# Motor4_PCIe.net
KiCad netlist of a schematic drawn in Altium Designer
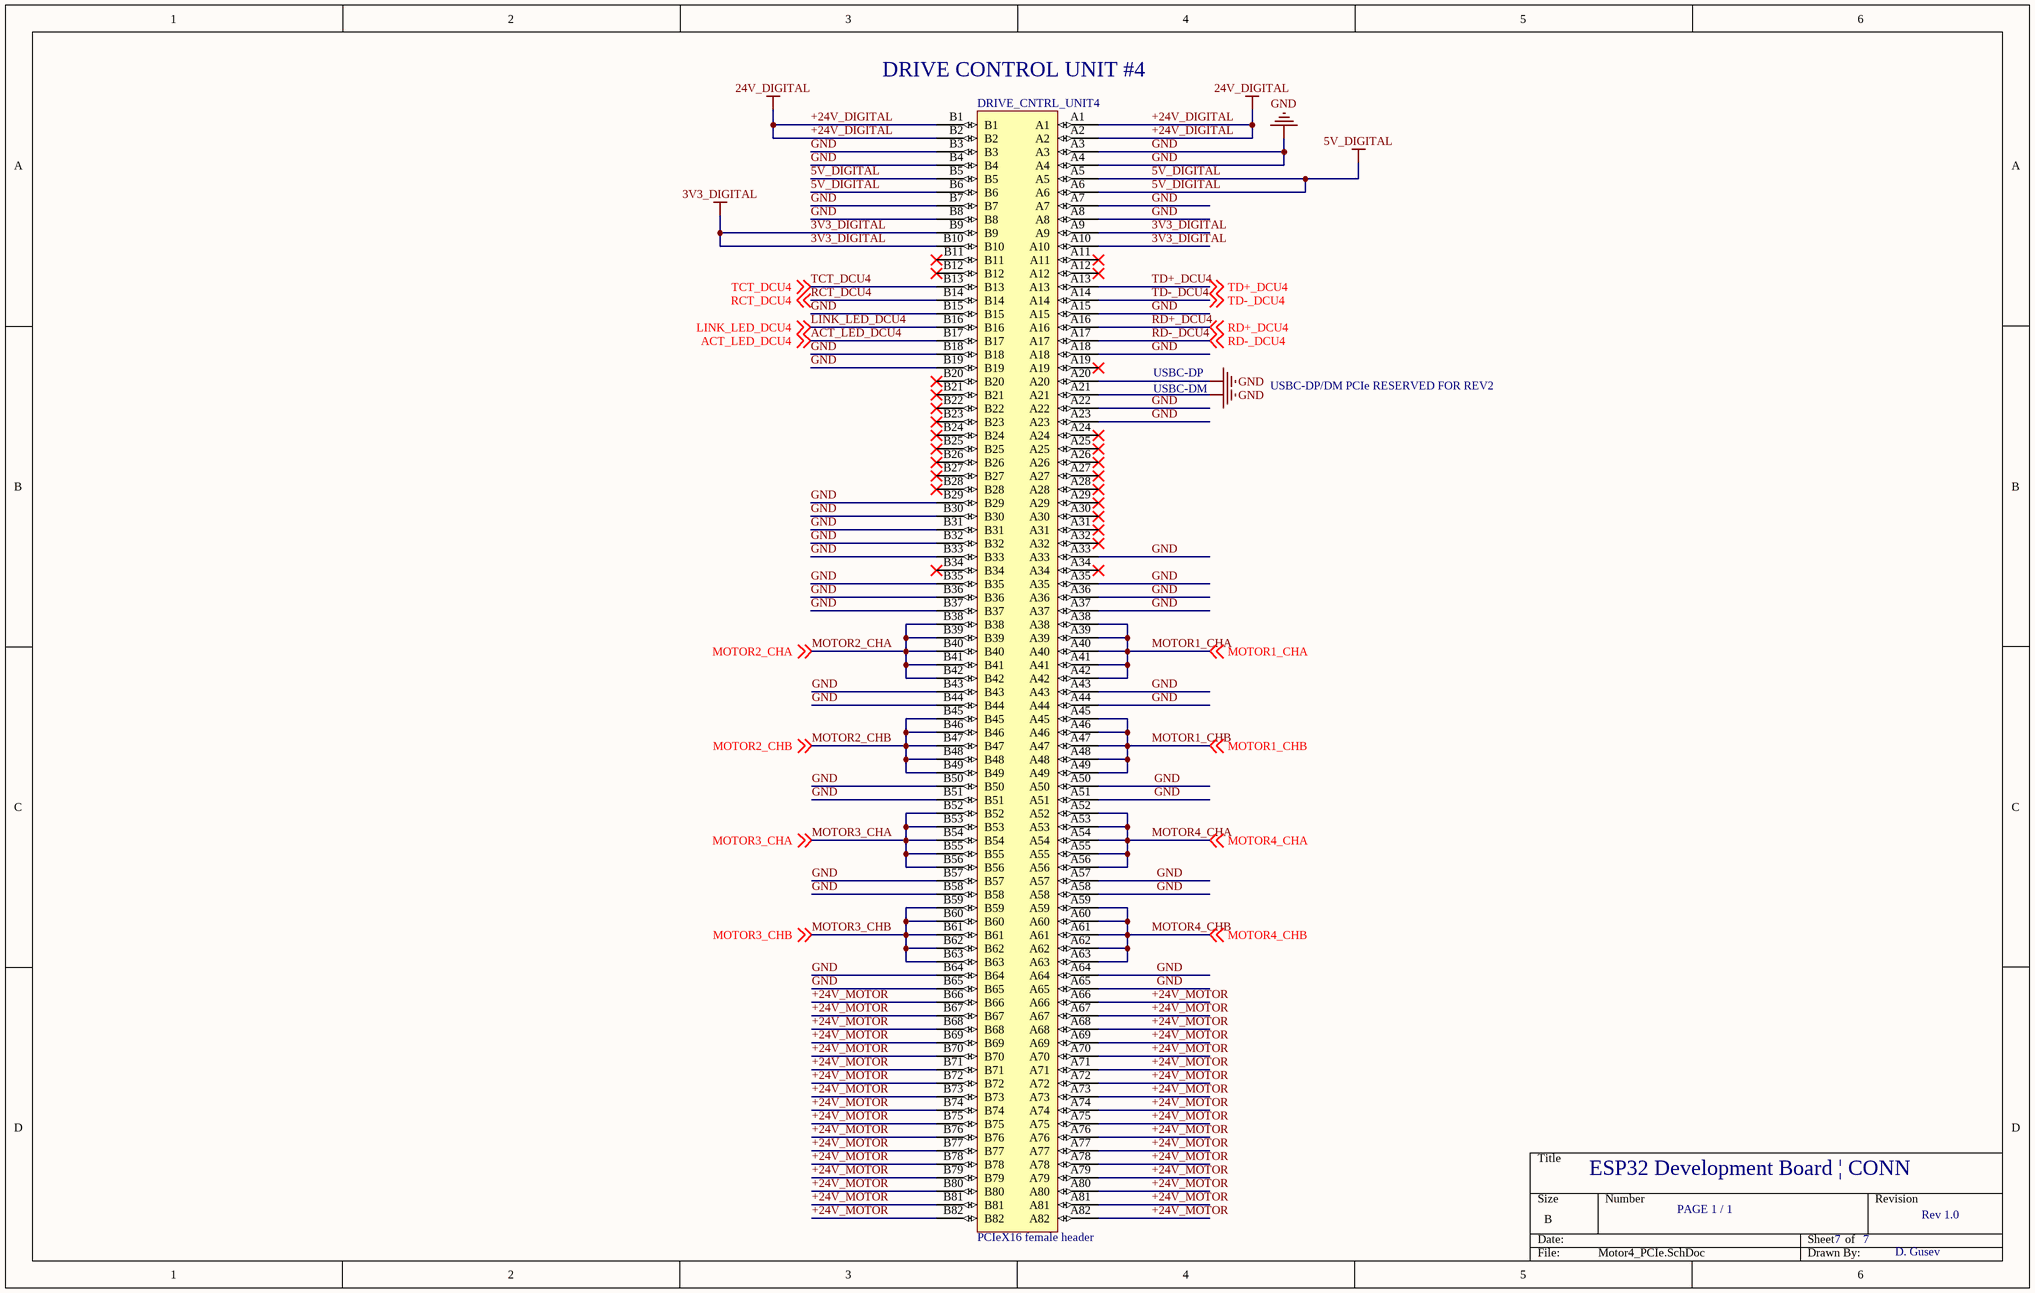
[diagram p0: Motor4_PCIe.SchDoc]

(export (version "E")
  (design (tool "Eeschema 10.0.6"))
  (components
    (comp (ref "DRIVE_CNTRL_UNIT4")
      (value "PCIeX16 female header")
      (footprint "SAMTEC_PCIE-164-02-X-D-TH")
      (description "164-position SAMTEC female header")
      (libsource (lib "ANTS-MotherBoard-B1") (part "PCIeX16 female header"))
    )
  )
  (nets
    (net (code "1") (name "/+24V_MOTOR") (class "Default")
      (node (ref "DRIVE_CNTRL_UNIT4") (pin "A66") (pinfunction "A66_A66") (pintype "bidirectional"))
      (node (ref "DRIVE_CNTRL_UNIT4") (pin "A67") (pinfunction "A67_A67") (pintype "bidirectional"))
      (node (ref "DRIVE_CNTRL_UNIT4") (pin "A68") (pinfunction "A68_A68") (pintype "bidirectional"))
      (node (ref "DRIVE_CNTRL_UNIT4") (pin "A69") (pinfunction "A69_A69") (pintype "bidirectional"))
      (node (ref "DRIVE_CNTRL_UNIT4") (pin "A70") (pinfunction "A70_A70") (pintype "bidirectional"))
      (node (ref "DRIVE_CNTRL_UNIT4") (pin "A71") (pinfunction "A71_A71") (pintype "bidirectional"))
      (node (ref "DRIVE_CNTRL_UNIT4") (pin "A72") (pinfunction "A72_A72") (pintype "bidirectional"))
      (node (ref "DRIVE_CNTRL_UNIT4") (pin "A73") (pinfunction "A73_A73") (pintype "bidirectional"))
      (node (ref "DRIVE_CNTRL_UNIT4") (pin "A74") (pinfunction "A74_A74") (pintype "bidirectional"))
      (node (ref "DRIVE_CNTRL_UNIT4") (pin "A75") (pinfunction "A75_A75") (pintype "bidirectional"))
      (node (ref "DRIVE_CNTRL_UNIT4") (pin "A76") (pinfunction "A76_A76") (pintype "bidirectional"))
      (node (ref "DRIVE_CNTRL_UNIT4") (pin "A77") (pinfunction "A77_A77") (pintype "bidirectional"))
      (node (ref "DRIVE_CNTRL_UNIT4") (pin "A78") (pinfunction "A78_A78") (pintype "bidirectional"))
      (node (ref "DRIVE_CNTRL_UNIT4") (pin "A79") (pinfunction "A79_A79") (pintype "bidirectional"))
      (node (ref "DRIVE_CNTRL_UNIT4") (pin "A80") (pinfunction "A80_A80") (pintype "bidirectional"))
      (node (ref "DRIVE_CNTRL_UNIT4") (pin "A81") (pinfunction "A81_A81") (pintype "bidirectional"))
      (node (ref "DRIVE_CNTRL_UNIT4") (pin "A82") (pinfunction "A82_A82") (pintype "bidirectional"))
      (node (ref "DRIVE_CNTRL_UNIT4") (pin "B66") (pinfunction "B66_B66") (pintype "bidirectional"))
      (node (ref "DRIVE_CNTRL_UNIT4") (pin "B67") (pinfunction "B67_B67") (pintype "bidirectional"))
      (node (ref "DRIVE_CNTRL_UNIT4") (pin "B68") (pinfunction "B68_B68") (pintype "bidirectional"))
      (node (ref "DRIVE_CNTRL_UNIT4") (pin "B69") (pinfunction "B69_B69") (pintype "bidirectional"))
      (node (ref "DRIVE_CNTRL_UNIT4") (pin "B70") (pinfunction "B70_B70") (pintype "bidirectional"))
      (node (ref "DRIVE_CNTRL_UNIT4") (pin "B71") (pinfunction "B71_B71") (pintype "bidirectional"))
      (node (ref "DRIVE_CNTRL_UNIT4") (pin "B72") (pinfunction "B72_B72") (pintype "bidirectional"))
      (node (ref "DRIVE_CNTRL_UNIT4") (pin "B73") (pinfunction "B73_B73") (pintype "bidirectional"))
      (node (ref "DRIVE_CNTRL_UNIT4") (pin "B74") (pinfunction "B74_B74") (pintype "bidirectional"))
      (node (ref "DRIVE_CNTRL_UNIT4") (pin "B75") (pinfunction "B75_B75") (pintype "bidirectional"))
      (node (ref "DRIVE_CNTRL_UNIT4") (pin "B76") (pinfunction "B76_B76") (pintype "bidirectional"))
      (node (ref "DRIVE_CNTRL_UNIT4") (pin "B77") (pinfunction "B77_B77") (pintype "bidirectional"))
      (node (ref "DRIVE_CNTRL_UNIT4") (pin "B78") (pinfunction "B78_B78") (pintype "bidirectional"))
      (node (ref "DRIVE_CNTRL_UNIT4") (pin "B79") (pinfunction "B79_B79") (pintype "bidirectional"))
      (node (ref "DRIVE_CNTRL_UNIT4") (pin "B80") (pinfunction "B80_B80") (pintype "bidirectional"))
      (node (ref "DRIVE_CNTRL_UNIT4") (pin "B81") (pinfunction "B81_B81") (pintype "bidirectional"))
      (node (ref "DRIVE_CNTRL_UNIT4") (pin "B82") (pinfunction "B82_B82") (pintype "bidirectional"))
    )
    (net (code "2") (name "3V3_DIGITAL") (class "Default")
      (node (ref "DRIVE_CNTRL_UNIT4") (pin "A10") (pinfunction "A10_A10") (pintype "bidirectional"))
      (node (ref "DRIVE_CNTRL_UNIT4") (pin "A9") (pinfunction "A9_A9") (pintype "bidirectional"))
      (node (ref "DRIVE_CNTRL_UNIT4") (pin "B10") (pinfunction "B10_B10") (pintype "bidirectional"))
      (node (ref "DRIVE_CNTRL_UNIT4") (pin "B9") (pinfunction "B9_B9") (pintype "bidirectional"))
    )
    (net (code "3") (name "5V_DIGITAL") (class "Default")
      (node (ref "DRIVE_CNTRL_UNIT4") (pin "A5") (pinfunction "A5_A5") (pintype "bidirectional"))
      (node (ref "DRIVE_CNTRL_UNIT4") (pin "A6") (pinfunction "A6_A6") (pintype "bidirectional"))
      (node (ref "DRIVE_CNTRL_UNIT4") (pin "B5") (pinfunction "B5_B5") (pintype "bidirectional"))
      (node (ref "DRIVE_CNTRL_UNIT4") (pin "B6") (pinfunction "B6_B6") (pintype "bidirectional"))
    )
    (net (code "4") (name "24V_DIGITAL") (class "Default")
      (node (ref "DRIVE_CNTRL_UNIT4") (pin "A1") (pinfunction "A1_A1") (pintype "bidirectional"))
      (node (ref "DRIVE_CNTRL_UNIT4") (pin "A2") (pinfunction "A2_A2") (pintype "bidirectional"))
      (node (ref "DRIVE_CNTRL_UNIT4") (pin "B1") (pinfunction "B1_B1") (pintype "bidirectional"))
      (node (ref "DRIVE_CNTRL_UNIT4") (pin "B2") (pinfunction "B2_B2") (pintype "bidirectional"))
    )
    (net (code "5") (name "ACT_LED_DCU4") (class "Default")
      (node (ref "DRIVE_CNTRL_UNIT4") (pin "B17") (pinfunction "B17_B17") (pintype "bidirectional"))
    )
    (net (code "6") (name "GND") (class "Default")
      (node (ref "DRIVE_CNTRL_UNIT4") (pin "A15") (pinfunction "A15_A15") (pintype "bidirectional"))
      (node (ref "DRIVE_CNTRL_UNIT4") (pin "A18") (pinfunction "A18_A18") (pintype "bidirectional"))
      (node (ref "DRIVE_CNTRL_UNIT4") (pin "A20") (pinfunction "A20_A20") (pintype "bidirectional"))
      (node (ref "DRIVE_CNTRL_UNIT4") (pin "A21") (pinfunction "A21_A21") (pintype "bidirectional"))
      (node (ref "DRIVE_CNTRL_UNIT4") (pin "A22") (pinfunction "A22_A22") (pintype "bidirectional"))
      (node (ref "DRIVE_CNTRL_UNIT4") (pin "A23") (pinfunction "A23_A23") (pintype "bidirectional"))
      (node (ref "DRIVE_CNTRL_UNIT4") (pin "A3") (pinfunction "A3_A3") (pintype "bidirectional"))
      (node (ref "DRIVE_CNTRL_UNIT4") (pin "A33") (pinfunction "A33_A33") (pintype "bidirectional"))
      (node (ref "DRIVE_CNTRL_UNIT4") (pin "A35") (pinfunction "A35_A35") (pintype "bidirectional"))
      (node (ref "DRIVE_CNTRL_UNIT4") (pin "A36") (pinfunction "A36_A36") (pintype "bidirectional"))
      (node (ref "DRIVE_CNTRL_UNIT4") (pin "A37") (pinfunction "A37_A37") (pintype "bidirectional"))
      (node (ref "DRIVE_CNTRL_UNIT4") (pin "A4") (pinfunction "A4_A4") (pintype "bidirectional"))
      (node (ref "DRIVE_CNTRL_UNIT4") (pin "A43") (pinfunction "A43_A43") (pintype "bidirectional"))
      (node (ref "DRIVE_CNTRL_UNIT4") (pin "A44") (pinfunction "A44_A44") (pintype "bidirectional"))
      (node (ref "DRIVE_CNTRL_UNIT4") (pin "A50") (pinfunction "A50_A50") (pintype "bidirectional"))
      (node (ref "DRIVE_CNTRL_UNIT4") (pin "A51") (pinfunction "A51_A51") (pintype "bidirectional"))
      (node (ref "DRIVE_CNTRL_UNIT4") (pin "A57") (pinfunction "A57_A57") (pintype "bidirectional"))
      (node (ref "DRIVE_CNTRL_UNIT4") (pin "A58") (pinfunction "A58_A58") (pintype "bidirectional"))
      (node (ref "DRIVE_CNTRL_UNIT4") (pin "A64") (pinfunction "A64_A64") (pintype "bidirectional"))
      (node (ref "DRIVE_CNTRL_UNIT4") (pin "A65") (pinfunction "A65_A65") (pintype "bidirectional"))
      (node (ref "DRIVE_CNTRL_UNIT4") (pin "A7") (pinfunction "A7_A7") (pintype "bidirectional"))
      (node (ref "DRIVE_CNTRL_UNIT4") (pin "A8") (pinfunction "A8_A8") (pintype "bidirectional"))
      (node (ref "DRIVE_CNTRL_UNIT4") (pin "B15") (pinfunction "B15_B15") (pintype "bidirectional"))
      (node (ref "DRIVE_CNTRL_UNIT4") (pin "B18") (pinfunction "B18_B18") (pintype "bidirectional"))
      (node (ref "DRIVE_CNTRL_UNIT4") (pin "B19") (pinfunction "B19_B19") (pintype "bidirectional"))
      (node (ref "DRIVE_CNTRL_UNIT4") (pin "B29") (pinfunction "B29_B29") (pintype "bidirectional"))
      (node (ref "DRIVE_CNTRL_UNIT4") (pin "B3") (pinfunction "B3_B3") (pintype "bidirectional"))
      (node (ref "DRIVE_CNTRL_UNIT4") (pin "B30") (pinfunction "B30_B30") (pintype "bidirectional"))
      (node (ref "DRIVE_CNTRL_UNIT4") (pin "B31") (pinfunction "B31_B31") (pintype "bidirectional"))
      (node (ref "DRIVE_CNTRL_UNIT4") (pin "B32") (pinfunction "B32_B32") (pintype "bidirectional"))
      (node (ref "DRIVE_CNTRL_UNIT4") (pin "B33") (pinfunction "B33_B33") (pintype "bidirectional"))
      (node (ref "DRIVE_CNTRL_UNIT4") (pin "B35") (pinfunction "B35_B35") (pintype "bidirectional"))
      (node (ref "DRIVE_CNTRL_UNIT4") (pin "B36") (pinfunction "B36_B36") (pintype "bidirectional"))
      (node (ref "DRIVE_CNTRL_UNIT4") (pin "B37") (pinfunction "B37_B37") (pintype "bidirectional"))
      (node (ref "DRIVE_CNTRL_UNIT4") (pin "B4") (pinfunction "B4_B4") (pintype "bidirectional"))
      (node (ref "DRIVE_CNTRL_UNIT4") (pin "B43") (pinfunction "B43_B43") (pintype "bidirectional"))
      (node (ref "DRIVE_CNTRL_UNIT4") (pin "B44") (pinfunction "B44_B44") (pintype "bidirectional"))
      (node (ref "DRIVE_CNTRL_UNIT4") (pin "B50") (pinfunction "B50_B50") (pintype "bidirectional"))
      (node (ref "DRIVE_CNTRL_UNIT4") (pin "B51") (pinfunction "B51_B51") (pintype "bidirectional"))
      (node (ref "DRIVE_CNTRL_UNIT4") (pin "B57") (pinfunction "B57_B57") (pintype "bidirectional"))
      (node (ref "DRIVE_CNTRL_UNIT4") (pin "B58") (pinfunction "B58_B58") (pintype "bidirectional"))
      (node (ref "DRIVE_CNTRL_UNIT4") (pin "B64") (pinfunction "B64_B64") (pintype "bidirectional"))
      (node (ref "DRIVE_CNTRL_UNIT4") (pin "B65") (pinfunction "B65_B65") (pintype "bidirectional"))
      (node (ref "DRIVE_CNTRL_UNIT4") (pin "B7") (pinfunction "B7_B7") (pintype "bidirectional"))
      (node (ref "DRIVE_CNTRL_UNIT4") (pin "B8") (pinfunction "B8_B8") (pintype "bidirectional"))
    )
    (net (code "7") (name "LINK_LED_DCU4") (class "Default")
      (node (ref "DRIVE_CNTRL_UNIT4") (pin "B16") (pinfunction "B16_B16") (pintype "bidirectional"))
    )
    (net (code "8") (name "MOTOR1_CHA") (class "Default")
      (node (ref "DRIVE_CNTRL_UNIT4") (pin "A38") (pinfunction "A38_A38") (pintype "bidirectional"))
      (node (ref "DRIVE_CNTRL_UNIT4") (pin "A39") (pinfunction "A39_A39") (pintype "bidirectional"))
      (node (ref "DRIVE_CNTRL_UNIT4") (pin "A40") (pinfunction "A40_A40") (pintype "bidirectional"))
      (node (ref "DRIVE_CNTRL_UNIT4") (pin "A41") (pinfunction "A41_A41") (pintype "bidirectional"))
      (node (ref "DRIVE_CNTRL_UNIT4") (pin "A42") (pinfunction "A42_A42") (pintype "bidirectional"))
    )
    (net (code "9") (name "MOTOR1_CHB") (class "Default")
      (node (ref "DRIVE_CNTRL_UNIT4") (pin "A45") (pinfunction "A45_A45") (pintype "bidirectional"))
      (node (ref "DRIVE_CNTRL_UNIT4") (pin "A46") (pinfunction "A46_A46") (pintype "bidirectional"))
      (node (ref "DRIVE_CNTRL_UNIT4") (pin "A47") (pinfunction "A47_A47") (pintype "bidirectional"))
      (node (ref "DRIVE_CNTRL_UNIT4") (pin "A48") (pinfunction "A48_A48") (pintype "bidirectional"))
      (node (ref "DRIVE_CNTRL_UNIT4") (pin "A49") (pinfunction "A49_A49") (pintype "bidirectional"))
    )
    (net (code "10") (name "MOTOR2_CHA") (class "Default")
      (node (ref "DRIVE_CNTRL_UNIT4") (pin "B38") (pinfunction "B38_B38") (pintype "bidirectional"))
      (node (ref "DRIVE_CNTRL_UNIT4") (pin "B39") (pinfunction "B39_B39") (pintype "bidirectional"))
      (node (ref "DRIVE_CNTRL_UNIT4") (pin "B40") (pinfunction "B40_B40") (pintype "bidirectional"))
      (node (ref "DRIVE_CNTRL_UNIT4") (pin "B41") (pinfunction "B41_B41") (pintype "bidirectional"))
      (node (ref "DRIVE_CNTRL_UNIT4") (pin "B42") (pinfunction "B42_B42") (pintype "bidirectional"))
    )
    (net (code "11") (name "MOTOR2_CHB") (class "Default")
      (node (ref "DRIVE_CNTRL_UNIT4") (pin "B45") (pinfunction "B45_B45") (pintype "bidirectional"))
      (node (ref "DRIVE_CNTRL_UNIT4") (pin "B46") (pinfunction "B46_B46") (pintype "bidirectional"))
      (node (ref "DRIVE_CNTRL_UNIT4") (pin "B47") (pinfunction "B47_B47") (pintype "bidirectional"))
      (node (ref "DRIVE_CNTRL_UNIT4") (pin "B48") (pinfunction "B48_B48") (pintype "bidirectional"))
      (node (ref "DRIVE_CNTRL_UNIT4") (pin "B49") (pinfunction "B49_B49") (pintype "bidirectional"))
    )
    (net (code "12") (name "MOTOR3_CHA") (class "Default")
      (node (ref "DRIVE_CNTRL_UNIT4") (pin "B52") (pinfunction "B52_B52") (pintype "bidirectional"))
      (node (ref "DRIVE_CNTRL_UNIT4") (pin "B53") (pinfunction "B53_B53") (pintype "bidirectional"))
      (node (ref "DRIVE_CNTRL_UNIT4") (pin "B54") (pinfunction "B54_B54") (pintype "bidirectional"))
      (node (ref "DRIVE_CNTRL_UNIT4") (pin "B55") (pinfunction "B55_B55") (pintype "bidirectional"))
      (node (ref "DRIVE_CNTRL_UNIT4") (pin "B56") (pinfunction "B56_B56") (pintype "bidirectional"))
    )
    (net (code "13") (name "MOTOR3_CHB") (class "Default")
      (node (ref "DRIVE_CNTRL_UNIT4") (pin "B59") (pinfunction "B59_B59") (pintype "bidirectional"))
      (node (ref "DRIVE_CNTRL_UNIT4") (pin "B60") (pinfunction "B60_B60") (pintype "bidirectional"))
      (node (ref "DRIVE_CNTRL_UNIT4") (pin "B61") (pinfunction "B61_B61") (pintype "bidirectional"))
      (node (ref "DRIVE_CNTRL_UNIT4") (pin "B62") (pinfunction "B62_B62") (pintype "bidirectional"))
      (node (ref "DRIVE_CNTRL_UNIT4") (pin "B63") (pinfunction "B63_B63") (pintype "bidirectional"))
    )
    (net (code "14") (name "MOTOR4_CHA") (class "Default")
      (node (ref "DRIVE_CNTRL_UNIT4") (pin "A52") (pinfunction "A52_A52") (pintype "bidirectional"))
      (node (ref "DRIVE_CNTRL_UNIT4") (pin "A53") (pinfunction "A53_A53") (pintype "bidirectional"))
      (node (ref "DRIVE_CNTRL_UNIT4") (pin "A54") (pinfunction "A54_A54") (pintype "bidirectional"))
      (node (ref "DRIVE_CNTRL_UNIT4") (pin "A55") (pinfunction "A55_A55") (pintype "bidirectional"))
      (node (ref "DRIVE_CNTRL_UNIT4") (pin "A56") (pinfunction "A56_A56") (pintype "bidirectional"))
    )
    (net (code "15") (name "MOTOR4_CHB") (class "Default")
      (node (ref "DRIVE_CNTRL_UNIT4") (pin "A59") (pinfunction "A59_A59") (pintype "bidirectional"))
      (node (ref "DRIVE_CNTRL_UNIT4") (pin "A60") (pinfunction "A60_A60") (pintype "bidirectional"))
      (node (ref "DRIVE_CNTRL_UNIT4") (pin "A61") (pinfunction "A61_A61") (pintype "bidirectional"))
      (node (ref "DRIVE_CNTRL_UNIT4") (pin "A62") (pinfunction "A62_A62") (pintype "bidirectional"))
      (node (ref "DRIVE_CNTRL_UNIT4") (pin "A63") (pinfunction "A63_A63") (pintype "bidirectional"))
    )
    (net (code "16") (name "RCT_DCU4") (class "Default")
      (node (ref "DRIVE_CNTRL_UNIT4") (pin "B14") (pinfunction "B14_B14") (pintype "bidirectional"))
    )
    (net (code "17") (name "RD+_DCU4") (class "Default")
      (node (ref "DRIVE_CNTRL_UNIT4") (pin "A16") (pinfunction "A16_A16") (pintype "bidirectional"))
    )
    (net (code "18") (name "RD-_DCU4") (class "Default")
      (node (ref "DRIVE_CNTRL_UNIT4") (pin "A17") (pinfunction "A17_A17") (pintype "bidirectional"))
    )
    (net (code "19") (name "TCT_DCU4") (class "Default")
      (node (ref "DRIVE_CNTRL_UNIT4") (pin "B13") (pinfunction "B13_B13") (pintype "bidirectional"))
    )
    (net (code "20") (name "TD+_DCU4") (class "Default")
      (node (ref "DRIVE_CNTRL_UNIT4") (pin "A13") (pinfunction "A13_A13") (pintype "bidirectional"))
    )
    (net (code "21") (name "TD-_DCU4") (class "Default")
      (node (ref "DRIVE_CNTRL_UNIT4") (pin "A14") (pinfunction "A14_A14") (pintype "bidirectional"))
    )
    (net (code "22") (name "unconnected-(DRIVE_CNTRL_UNIT4-PadA11)") (class "Default")
      (node (ref "DRIVE_CNTRL_UNIT4") (pin "A11") (pinfunction "A11_A11") (pintype "bidirectional+no_connect"))
    )
    (net (code "23") (name "unconnected-(DRIVE_CNTRL_UNIT4-PadA12)") (class "Default")
      (node (ref "DRIVE_CNTRL_UNIT4") (pin "A12") (pinfunction "A12_A12") (pintype "bidirectional+no_connect"))
    )
    (net (code "24") (name "unconnected-(DRIVE_CNTRL_UNIT4-PadA19)") (class "Default")
      (node (ref "DRIVE_CNTRL_UNIT4") (pin "A19") (pinfunction "A19_A19") (pintype "bidirectional+no_connect"))
    )
    (net (code "25") (name "unconnected-(DRIVE_CNTRL_UNIT4-PadA24)") (class "Default")
      (node (ref "DRIVE_CNTRL_UNIT4") (pin "A24") (pinfunction "A24_A24") (pintype "bidirectional+no_connect"))
    )
    (net (code "26") (name "unconnected-(DRIVE_CNTRL_UNIT4-PadA25)") (class "Default")
      (node (ref "DRIVE_CNTRL_UNIT4") (pin "A25") (pinfunction "A25_A25") (pintype "bidirectional+no_connect"))
    )
    (net (code "27") (name "unconnected-(DRIVE_CNTRL_UNIT4-PadA26)") (class "Default")
      (node (ref "DRIVE_CNTRL_UNIT4") (pin "A26") (pinfunction "A26_A26") (pintype "bidirectional+no_connect"))
    )
    (net (code "28") (name "unconnected-(DRIVE_CNTRL_UNIT4-PadA27)") (class "Default")
      (node (ref "DRIVE_CNTRL_UNIT4") (pin "A27") (pinfunction "A27_A27") (pintype "bidirectional+no_connect"))
    )
    (net (code "29") (name "unconnected-(DRIVE_CNTRL_UNIT4-PadA28)") (class "Default")
      (node (ref "DRIVE_CNTRL_UNIT4") (pin "A28") (pinfunction "A28_A28") (pintype "bidirectional+no_connect"))
    )
    (net (code "30") (name "unconnected-(DRIVE_CNTRL_UNIT4-PadA29)") (class "Default")
      (node (ref "DRIVE_CNTRL_UNIT4") (pin "A29") (pinfunction "A29_A29") (pintype "bidirectional+no_connect"))
    )
    (net (code "31") (name "unconnected-(DRIVE_CNTRL_UNIT4-PadA30)") (class "Default")
      (node (ref "DRIVE_CNTRL_UNIT4") (pin "A30") (pinfunction "A30_A30") (pintype "bidirectional+no_connect"))
    )
    (net (code "32") (name "unconnected-(DRIVE_CNTRL_UNIT4-PadA31)") (class "Default")
      (node (ref "DRIVE_CNTRL_UNIT4") (pin "A31") (pinfunction "A31_A31") (pintype "bidirectional+no_connect"))
    )
    (net (code "33") (name "unconnected-(DRIVE_CNTRL_UNIT4-PadA32)") (class "Default")
      (node (ref "DRIVE_CNTRL_UNIT4") (pin "A32") (pinfunction "A32_A32") (pintype "bidirectional+no_connect"))
    )
    (net (code "34") (name "unconnected-(DRIVE_CNTRL_UNIT4-PadA34)") (class "Default")
      (node (ref "DRIVE_CNTRL_UNIT4") (pin "A34") (pinfunction "A34_A34") (pintype "bidirectional+no_connect"))
    )
    (net (code "35") (name "unconnected-(DRIVE_CNTRL_UNIT4-PadB11)") (class "Default")
      (node (ref "DRIVE_CNTRL_UNIT4") (pin "B11") (pinfunction "B11_B11") (pintype "bidirectional+no_connect"))
    )
    (net (code "36") (name "unconnected-(DRIVE_CNTRL_UNIT4-PadB12)") (class "Default")
      (node (ref "DRIVE_CNTRL_UNIT4") (pin "B12") (pinfunction "B12_B12") (pintype "bidirectional+no_connect"))
    )
    (net (code "37") (name "unconnected-(DRIVE_CNTRL_UNIT4-PadB20)") (class "Default")
      (node (ref "DRIVE_CNTRL_UNIT4") (pin "B20") (pinfunction "B20_B20") (pintype "bidirectional+no_connect"))
    )
    (net (code "38") (name "unconnected-(DRIVE_CNTRL_UNIT4-PadB21)") (class "Default")
      (node (ref "DRIVE_CNTRL_UNIT4") (pin "B21") (pinfunction "B21_B21") (pintype "bidirectional+no_connect"))
    )
    (net (code "39") (name "unconnected-(DRIVE_CNTRL_UNIT4-PadB22)") (class "Default")
      (node (ref "DRIVE_CNTRL_UNIT4") (pin "B22") (pinfunction "B22_B22") (pintype "bidirectional+no_connect"))
    )
    (net (code "40") (name "unconnected-(DRIVE_CNTRL_UNIT4-PadB23)") (class "Default")
      (node (ref "DRIVE_CNTRL_UNIT4") (pin "B23") (pinfunction "B23_B23") (pintype "bidirectional+no_connect"))
    )
    (net (code "41") (name "unconnected-(DRIVE_CNTRL_UNIT4-PadB24)") (class "Default")
      (node (ref "DRIVE_CNTRL_UNIT4") (pin "B24") (pinfunction "B24_B24") (pintype "bidirectional+no_connect"))
    )
    (net (code "42") (name "unconnected-(DRIVE_CNTRL_UNIT4-PadB25)") (class "Default")
      (node (ref "DRIVE_CNTRL_UNIT4") (pin "B25") (pinfunction "B25_B25") (pintype "bidirectional+no_connect"))
    )
    (net (code "43") (name "unconnected-(DRIVE_CNTRL_UNIT4-PadB26)") (class "Default")
      (node (ref "DRIVE_CNTRL_UNIT4") (pin "B26") (pinfunction "B26_B26") (pintype "bidirectional+no_connect"))
    )
    (net (code "44") (name "unconnected-(DRIVE_CNTRL_UNIT4-PadB27)") (class "Default")
      (node (ref "DRIVE_CNTRL_UNIT4") (pin "B27") (pinfunction "B27_B27") (pintype "bidirectional+no_connect"))
    )
    (net (code "45") (name "unconnected-(DRIVE_CNTRL_UNIT4-PadB28)") (class "Default")
      (node (ref "DRIVE_CNTRL_UNIT4") (pin "B28") (pinfunction "B28_B28") (pintype "bidirectional+no_connect"))
    )
    (net (code "46") (name "unconnected-(DRIVE_CNTRL_UNIT4-PadB34)") (class "Default")
      (node (ref "DRIVE_CNTRL_UNIT4") (pin "B34") (pinfunction "B34_B34") (pintype "bidirectional+no_connect"))
    )
  )
)
